# Sheet.net
KiCad netlist of a schematic drawn in Altium Designer
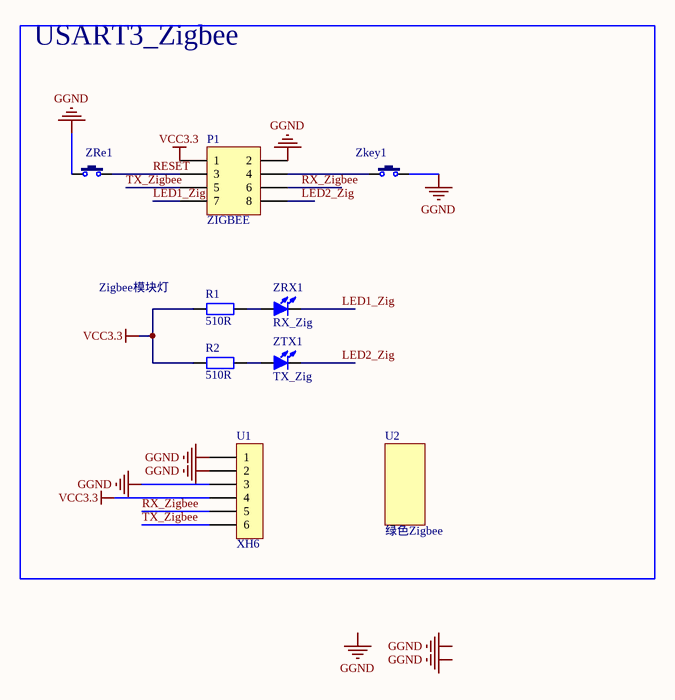
[diagram p0: Sheet.SchDoc]

(export (version "E")
  (design (tool "Eeschema 10.0.6"))
  (components
    (comp (ref "P1")
      (value "ZIGBEE")
      (footprint "Zigbee_DTK_DRF1609H-DIP")
      (description "Header, 4-Pin, Dual row")
      (fields (field (name "PUBLISHER") "Altium Limited"))
      (libsource (lib "Miscellaneous Connectors") (part "Header 4X2"))
    )
    (comp (ref "R1")
      (value "510R")
      (footprint "R 0805_M")
      (description "贴片电阻")
      (fields (field (name "版权归属") "黎明电子style"))
      (libsource (lib "电阻-电容-电感") (part "R"))
    )
    (comp (ref "R2")
      (value "510R")
      (footprint "R 0805_M")
      (description "贴片电阻")
      (fields (field (name "版权归属") "黎明电子style"))
      (libsource (lib "电阻-电容-电感") (part "R"))
    )
    (comp (ref "U1") (value "XH6") (footprint "XH6/2.54mm/180") (libsource (lib "XH，VH") (part "XH6")))
    (comp (ref "U2") (value "绿色Zigbee") (footprint "Zigbee_绿色") (libsource (lib "Schlib2") (part "绿色Zigbee")))
    (comp (ref "Zkey1")
      (value "ZigReset")
      (footprint "SW DIP-6*6*5")
      (description "3x6轻触开关")
      (fields (field (name "版权归属") "黎明电子style"))
      (libsource (lib "按键-开关") (part "TSW 3x6"))
    )
    (comp (ref "ZRe1")
      (value "ZigReset")
      (footprint "SW DIP-6*6*5")
      (description "3x6轻触开关")
      (fields (field (name "版权归属") "黎明电子style"))
      (libsource (lib "按键-开关") (part "TSW 3x6"))
    )
    (comp (ref "ZRX1")
      (value "RX_Zig")
      (footprint "LED 0805R")
      (description "贴片LED")
      (fields (field (name "版权归属") "黎明电子style"))
      (libsource (lib "LED") (part "LED-SMD"))
    )
    (comp (ref "ZTX1")
      (value "TX_Zig")
      (footprint "LED 0805R")
      (description "贴片LED")
      (fields (field (name "版权归属") "黎明电子style"))
      (libsource (lib "LED") (part "LED-SMD"))
    )
  )
  (nets
    (net (code "1") (name "/LED1_Zig") (class "Default")
      (node (ref "P1") (pin "7") (pinfunction "7_7") (pintype "passive"))
      (node (ref "ZRX1") (pin "2") (pinfunction "K_2") (pintype "passive"))
    )
    (net (code "2") (name "/LED2_Zig") (class "Default")
      (node (ref "P1") (pin "8") (pinfunction "8_8") (pintype "passive"))
      (node (ref "ZTX1") (pin "2") (pinfunction "K_2") (pintype "passive"))
    )
    (net (code "3") (name "/RESET") (class "Default")
      (node (ref "P1") (pin "3") (pinfunction "3_3") (pintype "passive"))
      (node (ref "ZRe1") (pin "2") (pinfunction "2_2") (pintype "passive"))
    )
    (net (code "4") (name "/RX_Zigbee") (class "Default")
      (node (ref "P1") (pin "6") (pinfunction "6_6") (pintype "passive"))
      (node (ref "U1") (pin "5") (pinfunction "5_5") (pintype "passive"))
    )
    (net (code "5") (name "/TX_Zigbee") (class "Default")
      (node (ref "P1") (pin "5") (pinfunction "5_5") (pintype "passive"))
      (node (ref "U1") (pin "6") (pinfunction "6_6") (pintype "passive"))
    )
    (net (code "6") (name "GGND") (class "Default")
      (node (ref "P1") (pin "2") (pinfunction "2_2") (pintype "passive"))
      (node (ref "U1") (pin "1") (pinfunction "1_1") (pintype "passive"))
      (node (ref "U1") (pin "2") (pinfunction "2_2") (pintype "passive"))
      (node (ref "U1") (pin "3") (pinfunction "3_3") (pintype "passive"))
      (node (ref "ZRe1") (pin "1") (pinfunction "1_1") (pintype "passive"))
      (node (ref "Zkey1") (pin "2") (pinfunction "2_2") (pintype "passive"))
    )
    (net (code "7") (name "Net-(P1-Pad4)") (class "Default")
      (node (ref "P1") (pin "4") (pinfunction "4_4") (pintype "passive"))
      (node (ref "Zkey1") (pin "1") (pinfunction "1_1") (pintype "passive"))
    )
    (net (code "8") (name "Net-(ZRX1-A)") (class "Default")
      (node (ref "R1") (pin "1") (pinfunction "1_1") (pintype "passive"))
      (node (ref "ZRX1") (pin "1") (pinfunction "A_1") (pintype "passive"))
    )
    (net (code "9") (name "Net-(ZTX1-A)") (class "Default")
      (node (ref "R2") (pin "1") (pinfunction "1_1") (pintype "passive"))
      (node (ref "ZTX1") (pin "1") (pinfunction "A_1") (pintype "passive"))
    )
    (net (code "10") (name "VCC3.3") (class "Default")
      (node (ref "P1") (pin "1") (pinfunction "1_1") (pintype "passive"))
      (node (ref "R1") (pin "2") (pinfunction "2_2") (pintype "passive"))
      (node (ref "R2") (pin "2") (pinfunction "2_2") (pintype "passive"))
      (node (ref "U1") (pin "4") (pinfunction "4_4") (pintype "passive"))
    )
  )
)
